# Filamint_Schematic_V4.net
KiCad netlist of a schematic drawn in EAGLE
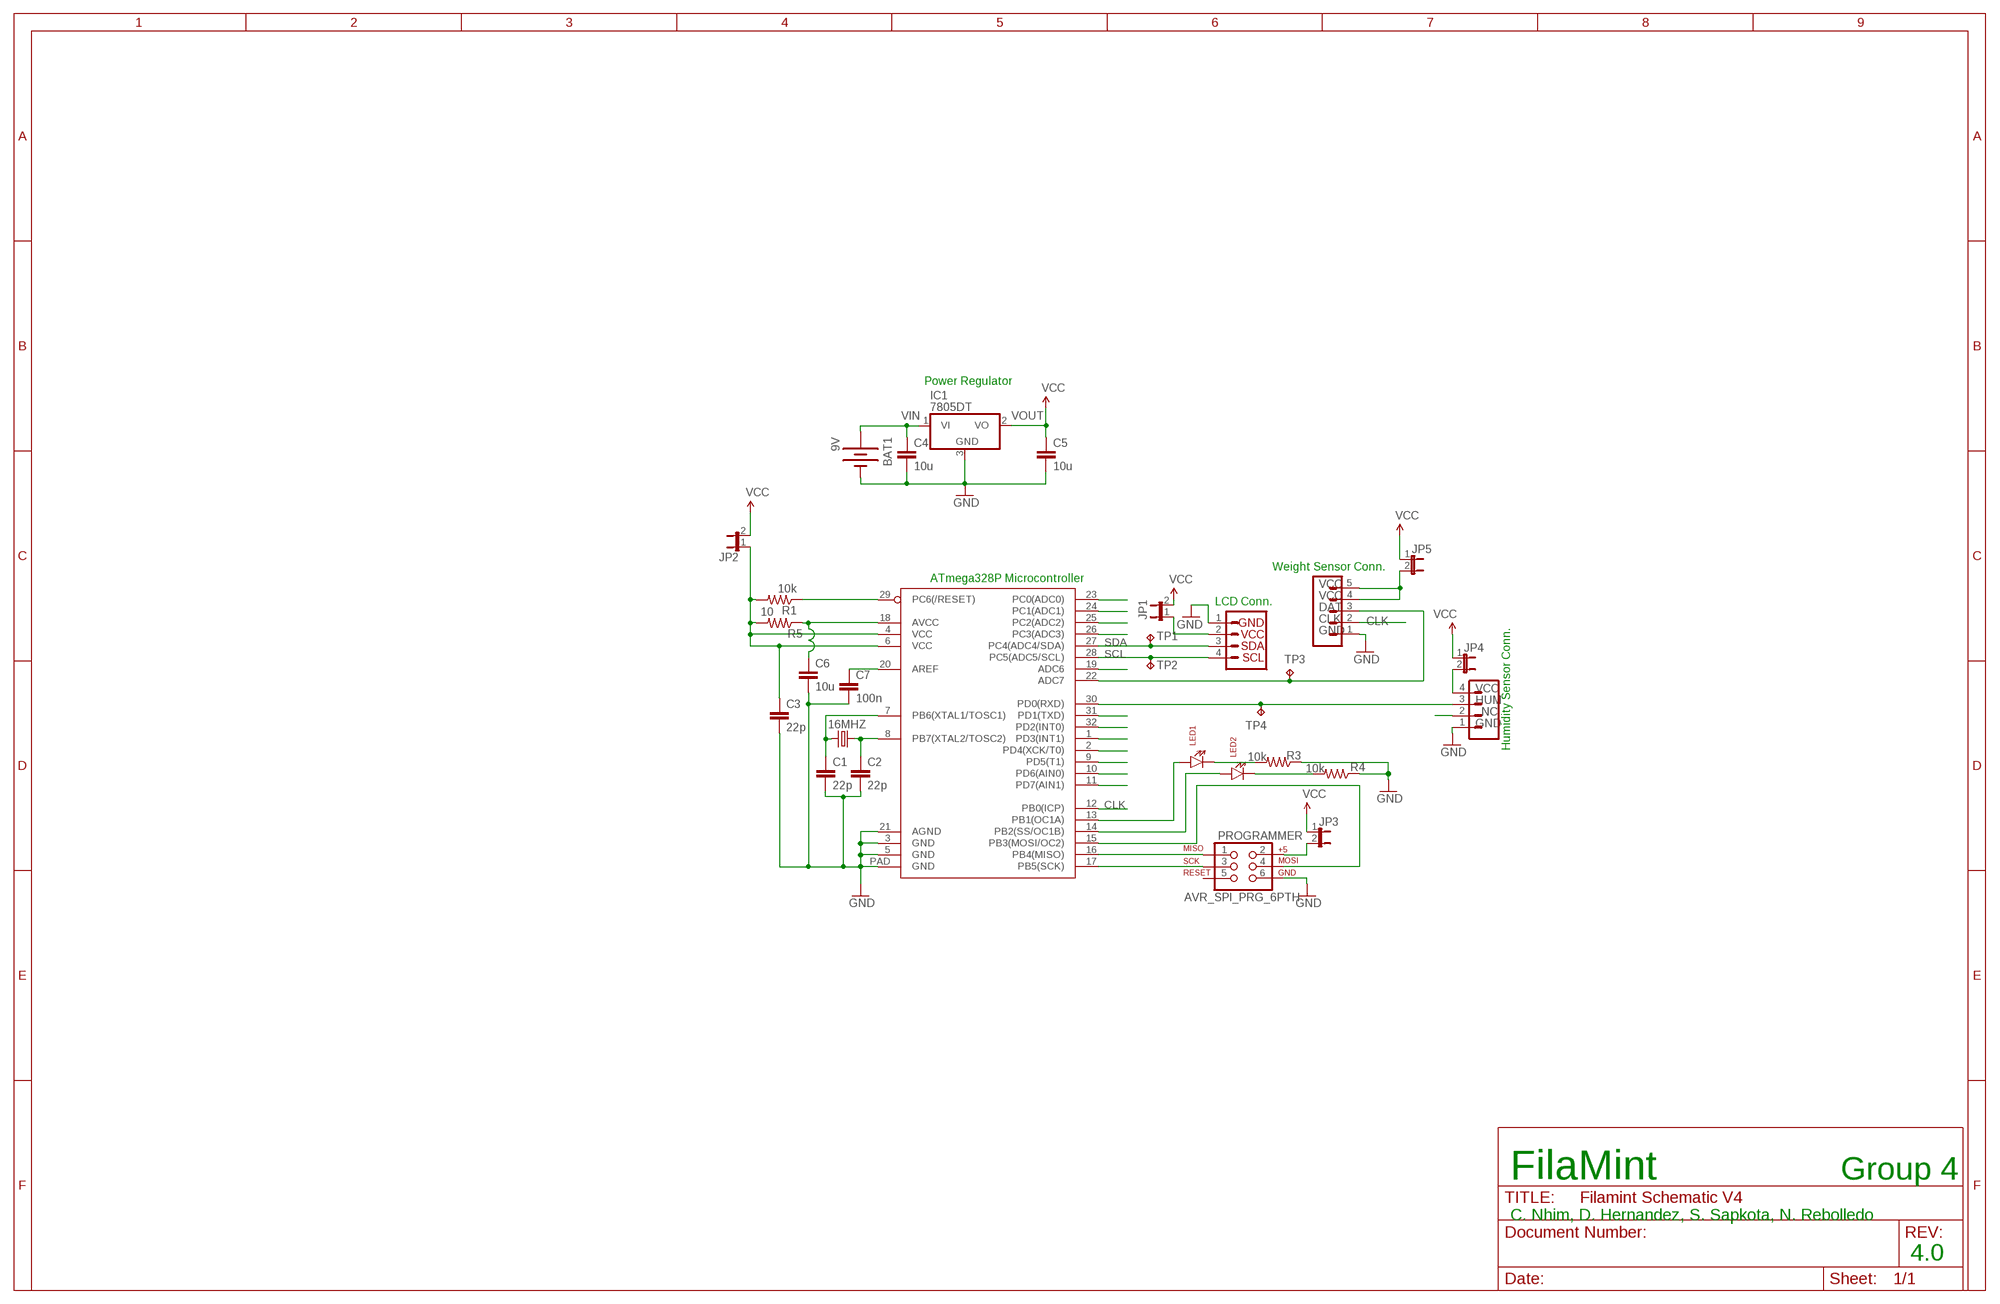
[diagram p0: schematic, sheet 1]

(export (version "E")
  (design (tool "Eeschema 10.0.6"))
  (components
    (comp (ref "16MHZ")
      (value "CSM-7X-DU")
      (footprint "eagle-import:CSM-7X-DU")
      (libsource (lib "eagle-import") (part "CSM-7X-DU"))
    )
    (comp (ref "BAT1")
      (value "9V")
      (footprint "eagle-import:BATTCON_9V")
      (libsource (lib "eagle-import") (part "BATTERY9V"))
    )
    (comp (ref "C1")
      (value "22p")
      (footprint "eagle-import:C025-024X044")
      (libsource (lib "eagle-import") (part "C-EU025-024X044"))
    )
    (comp (ref "C2")
      (value "22p")
      (footprint "eagle-import:C025-024X044")
      (libsource (lib "eagle-import") (part "C-EU025-024X044"))
    )
    (comp (ref "C3")
      (value "22p")
      (footprint "eagle-import:C025-024X044")
      (libsource (lib "eagle-import") (part "C-EU025-024X044"))
    )
    (comp (ref "C4")
      (value "10u")
      (footprint "eagle-import:C025-024X044")
      (libsource (lib "eagle-import") (part "C-EU025-024X044"))
    )
    (comp (ref "C5")
      (value "10u")
      (footprint "eagle-import:C025-024X044")
      (libsource (lib "eagle-import") (part "C-EU025-024X044"))
    )
    (comp (ref "C6")
      (value "10u")
      (footprint "eagle-import:C025-024X044")
      (libsource (lib "eagle-import") (part "C-EU025-024X044"))
    )
    (comp (ref "C7")
      (value "100n")
      (footprint "eagle-import:C025-024X044")
      (libsource (lib "eagle-import") (part "C-EU025-024X044"))
    )
    (comp (ref "DHT22")
      (value "M04SMD2")
      (footprint "eagle-import:1X04-1MM-RA")
      (libsource (lib "eagle-import") (part "M04SMD2"))
    )
    (comp (ref "HX711")
      (value "M05SMD")
      (footprint "eagle-import:1X05-1MM")
      (libsource (lib "eagle-import") (part "M05SMD"))
    )
    (comp (ref "IC1")
      (value "7805DT")
      (footprint "eagle-import:TO252")
      (libsource (lib "eagle-import") (part "78DT05"))
    )
    (comp (ref "JP1")
      (value "JP1E")
      (footprint "eagle-import:JP1")
      (libsource (lib "eagle-import") (part "JP1E"))
    )
    (comp (ref "JP2")
      (value "JP1E")
      (footprint "eagle-import:JP1")
      (libsource (lib "eagle-import") (part "JP1E"))
    )
    (comp (ref "JP3")
      (value "JP1E")
      (footprint "eagle-import:JP1")
      (libsource (lib "eagle-import") (part "JP1E"))
    )
    (comp (ref "JP4")
      (value "JP1E")
      (footprint "eagle-import:JP1")
      (libsource (lib "eagle-import") (part "JP1E"))
    )
    (comp (ref "JP5")
      (value "JP1E")
      (footprint "eagle-import:JP1")
      (libsource (lib "eagle-import") (part "JP1E"))
    )
    (comp (ref "LCD")
      (value "I2C_STANDARD")
      (footprint "eagle-import:1X04")
      (libsource (lib "eagle-import") (part "I2C_STANDARD"))
    )
    (comp (ref "LED1")
      (value "LTE-302")
      (footprint "eagle-import:LTE-302")
      (libsource (lib "eagle-import") (part "LTE-302"))
    )
    (comp (ref "LED2")
      (value "LTE-302")
      (footprint "eagle-import:LTE-302")
      (libsource (lib "eagle-import") (part "LTE-302"))
    )
    (comp (ref "MICROCONTROLLER")
      (value "ATMEGA328P_MLFMLF32")
      (footprint "eagle-import:MLF32-PAD")
      (libsource (lib "eagle-import") (part "ATMEGA328P_MLFMLF32"))
    )
    (comp (ref "PROGRAMMER")
      (value "AVR_SPI_PRG_6PTH")
      (footprint "eagle-import:2X3")
      (libsource (lib "eagle-import") (part "AVR_SPI_PRG_6PTH"))
    )
    (comp (ref "R1")
      (value "10k")
      (footprint "eagle-import:0204_5")
      (libsource (lib "eagle-import") (part "R-US_0204/5"))
    )
    (comp (ref "R3")
      (value "10k")
      (footprint "eagle-import:0204_5")
      (libsource (lib "eagle-import") (part "R-US_0204/5"))
    )
    (comp (ref "R4")
      (value "10k")
      (footprint "eagle-import:0204_5")
      (libsource (lib "eagle-import") (part "R-US_0204/5"))
    )
    (comp (ref "R5")
      (value "10")
      (footprint "eagle-import:0204_5")
      (libsource (lib "eagle-import") (part "R-US_0204/5"))
    )
    (comp (ref "TP1")
      (value "TPB1,27")
      (footprint "eagle-import:B1,27")
      (libsource (lib "eagle-import") (part "TPB1,27"))
    )
    (comp (ref "TP2")
      (value "TPB1,27")
      (footprint "eagle-import:B1,27")
      (libsource (lib "eagle-import") (part "TPB1,27"))
    )
    (comp (ref "TP3")
      (value "TPB1,27")
      (footprint "eagle-import:B1,27")
      (libsource (lib "eagle-import") (part "TPB1,27"))
    )
    (comp (ref "TP4")
      (value "TPB1,27")
      (footprint "eagle-import:B1,27")
      (libsource (lib "eagle-import") (part "TPB1,27"))
    )
  )
  (nets
    (net (code "1") (name "/CLK") (class "Default")
      (node (ref "HX711") (pin "2") (pinfunction "2_2") (pintype "passive"))
      (node (ref "MICROCONTROLLER") (pin "12") (pinfunction "PB0(ICP)_12") (pintype "bidirectional"))
    )
    (net (code "2") (name "/NC") (class "Default")
      (node (ref "DHT22") (pin "2") (pinfunction "2_2") (pintype "passive"))
    )
    (net (code "3") (name "/SCL") (class "Default")
      (node (ref "LCD") (pin "4") (pinfunction "4_4") (pintype "passive"))
      (node (ref "MICROCONTROLLER") (pin "28") (pinfunction "PC5(ADC5/SCL)_28") (pintype "bidirectional"))
      (node (ref "TP2") (pin "TP") (pinfunction "TP_TP") (pintype "input"))
    )
    (net (code "4") (name "/SDA") (class "Default")
      (node (ref "LCD") (pin "3") (pinfunction "3_3") (pintype "passive"))
      (node (ref "MICROCONTROLLER") (pin "27") (pinfunction "PC4(ADC4/SDA)_27") (pintype "bidirectional"))
      (node (ref "TP1") (pin "TP") (pinfunction "TP_TP") (pintype "input"))
    )
    (net (code "5") (name "/VIN") (class "Default")
      (node (ref "BAT1") (pin "+") (pinfunction "+_+") (pintype "power_in"))
      (node (ref "C4") (pin "1") (pinfunction "1_1") (pintype "passive"))
      (node (ref "IC1") (pin "1") (pinfunction "VI_1") (pintype "input"))
    )
    (net (code "6") (name "GND") (class "Default")
      (node (ref "BAT1") (pin "-") (pinfunction "-_-") (pintype "power_in"))
      (node (ref "C1") (pin "2") (pinfunction "2_2") (pintype "passive"))
      (node (ref "C2") (pin "2") (pinfunction "2_2") (pintype "passive"))
      (node (ref "C3") (pin "2") (pinfunction "2_2") (pintype "passive"))
      (node (ref "C4") (pin "2") (pinfunction "2_2") (pintype "passive"))
      (node (ref "C5") (pin "2") (pinfunction "2_2") (pintype "passive"))
      (node (ref "C6") (pin "2") (pinfunction "2_2") (pintype "passive"))
      (node (ref "C7") (pin "2") (pinfunction "2_2") (pintype "passive"))
      (node (ref "DHT22") (pin "1") (pinfunction "1_1") (pintype "passive"))
      (node (ref "HX711") (pin "1") (pinfunction "1_1") (pintype "passive"))
      (node (ref "IC1") (pin "3") (pinfunction "GND_3") (pintype "passive"))
      (node (ref "LCD") (pin "1") (pinfunction "1_1") (pintype "passive"))
      (node (ref "MICROCONTROLLER") (pin "21") (pinfunction "AGND_21") (pintype "bidirectional"))
      (node (ref "MICROCONTROLLER") (pin "3") (pinfunction "GND_3") (pintype "bidirectional"))
      (node (ref "MICROCONTROLLER") (pin "5") (pinfunction "GND_5") (pintype "bidirectional"))
      (node (ref "MICROCONTROLLER") (pin "PAD") (pinfunction "GND_PAD") (pintype "bidirectional"))
      (node (ref "PROGRAMMER") (pin "6") (pinfunction "6_6") (pintype "passive"))
      (node (ref "R3") (pin "1") (pinfunction "1_1") (pintype "passive"))
      (node (ref "R4") (pin "1") (pinfunction "1_1") (pintype "passive"))
    )
    (net (code "7") (name "Net-(C3-Pad1)") (class "Default")
      (node (ref "C3") (pin "1") (pinfunction "1_1") (pintype "passive"))
      (node (ref "JP2") (pin "1") (pinfunction "1_1") (pintype "passive"))
      (node (ref "MICROCONTROLLER") (pin "4") (pinfunction "VCC_4") (pintype "bidirectional"))
      (node (ref "MICROCONTROLLER") (pin "6") (pinfunction "VCC_6") (pintype "bidirectional"))
      (node (ref "R1") (pin "2") (pinfunction "2_2") (pintype "passive"))
      (node (ref "R5") (pin "2") (pinfunction "2_2") (pintype "passive"))
    )
    (net (code "8") (name "Net-(DHT22-Pad4)") (class "Default")
      (node (ref "DHT22") (pin "4") (pinfunction "4_4") (pintype "passive"))
      (node (ref "JP4") (pin "2") (pinfunction "2_2") (pintype "passive"))
    )
    (net (code "9") (name "Net-(HX711-Pad4)") (class "Default")
      (node (ref "HX711") (pin "4") (pinfunction "4_4") (pintype "passive"))
      (node (ref "HX711") (pin "5") (pinfunction "5_5") (pintype "passive"))
      (node (ref "JP5") (pin "2") (pinfunction "2_2") (pintype "passive"))
    )
    (net (code "10") (name "Net-(JP1-Pad1)") (class "Default")
      (node (ref "JP1") (pin "1") (pinfunction "1_1") (pintype "passive"))
      (node (ref "LCD") (pin "2") (pinfunction "2_2") (pintype "passive"))
    )
    (net (code "11") (name "Net-(JP3-Pad2)") (class "Default")
      (node (ref "JP3") (pin "2") (pinfunction "2_2") (pintype "passive"))
      (node (ref "PROGRAMMER") (pin "2") (pinfunction "2_2") (pintype "passive"))
    )
    (net (code "12") (name "Net-(LED1-PadC)") (class "Default")
      (node (ref "LED1") (pin "C") (pinfunction "C_C") (pintype "bidirectional"))
      (node (ref "R3") (pin "2") (pinfunction "2_2") (pintype "passive"))
    )
    (net (code "13") (name "Net-(LED2-PadC)") (class "Default")
      (node (ref "LED2") (pin "C") (pinfunction "C_C") (pintype "bidirectional"))
      (node (ref "R4") (pin "2") (pinfunction "2_2") (pintype "passive"))
    )
    (net (code "14") (name "Net-(MICROCONTROLLER-ADC7)") (class "Default")
      (node (ref "HX711") (pin "3") (pinfunction "3_3") (pintype "passive"))
      (node (ref "MICROCONTROLLER") (pin "22") (pinfunction "ADC7_22") (pintype "bidirectional"))
      (node (ref "TP3") (pin "TP") (pinfunction "TP_TP") (pintype "input"))
    )
    (net (code "15") (name "Net-(MICROCONTROLLER-AREF)") (class "Default")
      (node (ref "C7") (pin "1") (pinfunction "1_1") (pintype "passive"))
      (node (ref "MICROCONTROLLER") (pin "20") (pinfunction "AREF_20") (pintype "bidirectional"))
    )
    (net (code "16") (name "Net-(MICROCONTROLLER-AVCC)") (class "Default")
      (node (ref "C6") (pin "1") (pinfunction "1_1") (pintype "passive"))
      (node (ref "MICROCONTROLLER") (pin "18") (pinfunction "AVCC_18") (pintype "bidirectional"))
      (node (ref "R5") (pin "1") (pinfunction "1_1") (pintype "passive"))
    )
    (net (code "17") (name "Net-(MICROCONTROLLER-PB1(OC1A))") (class "Default")
      (node (ref "LED1") (pin "A") (pinfunction "A_A") (pintype "bidirectional"))
      (node (ref "MICROCONTROLLER") (pin "13") (pinfunction "PB1(OC1A)_13") (pintype "bidirectional"))
    )
    (net (code "18") (name "Net-(MICROCONTROLLER-PB2(SS{slash}OC1B))") (class "Default")
      (node (ref "LED2") (pin "A") (pinfunction "A_A") (pintype "bidirectional"))
      (node (ref "MICROCONTROLLER") (pin "14") (pinfunction "PB2(SS/OC1B)_14") (pintype "bidirectional"))
    )
    (net (code "19") (name "Net-(MICROCONTROLLER-PB3(MOSI{slash}OC2))") (class "Default")
      (node (ref "MICROCONTROLLER") (pin "15") (pinfunction "PB3(MOSI/OC2)_15") (pintype "bidirectional"))
      (node (ref "PROGRAMMER") (pin "4") (pinfunction "4_4") (pintype "passive"))
    )
    (net (code "20") (name "Net-(MICROCONTROLLER-PB4(MISO))") (class "Default")
      (node (ref "MICROCONTROLLER") (pin "16") (pinfunction "PB4(MISO)_16") (pintype "bidirectional"))
      (node (ref "PROGRAMMER") (pin "1") (pinfunction "1_1") (pintype "passive"))
    )
    (net (code "21") (name "Net-(MICROCONTROLLER-PB5(SCK))") (class "Default")
      (node (ref "MICROCONTROLLER") (pin "17") (pinfunction "PB5(SCK)_17") (pintype "bidirectional"))
      (node (ref "PROGRAMMER") (pin "3") (pinfunction "3_3") (pintype "passive"))
    )
    (net (code "22") (name "Net-(MICROCONTROLLER-PB6(XTAL1{slash}TOSC1))") (class "Default")
      (node (ref "16MHZ") (pin "2") (pinfunction "2_2") (pintype "passive"))
      (node (ref "C1") (pin "1") (pinfunction "1_1") (pintype "passive"))
      (node (ref "MICROCONTROLLER") (pin "7") (pinfunction "PB6(XTAL1/TOSC1)_7") (pintype "bidirectional"))
    )
    (net (code "23") (name "Net-(MICROCONTROLLER-PB7(XTAL2{slash}TOSC2))") (class "Default")
      (node (ref "16MHZ") (pin "1") (pinfunction "1_1") (pintype "passive"))
      (node (ref "C2") (pin "1") (pinfunction "1_1") (pintype "passive"))
      (node (ref "MICROCONTROLLER") (pin "8") (pinfunction "PB7(XTAL2/TOSC2)_8") (pintype "bidirectional"))
    )
    (net (code "24") (name "Net-(MICROCONTROLLER-PC6({slash}RESET))") (class "Default")
      (node (ref "MICROCONTROLLER") (pin "29") (pinfunction "PC6(/RESET)_29") (pintype "bidirectional"))
      (node (ref "R1") (pin "1") (pinfunction "1_1") (pintype "passive"))
    )
    (net (code "25") (name "Net-(MICROCONTROLLER-PD0(RXD))") (class "Default")
      (node (ref "DHT22") (pin "3") (pinfunction "3_3") (pintype "passive"))
      (node (ref "MICROCONTROLLER") (pin "30") (pinfunction "PD0(RXD)_30") (pintype "bidirectional"))
      (node (ref "TP4") (pin "TP") (pinfunction "TP_TP") (pintype "input"))
    )
    (net (code "26") (name "VCC") (class "Default")
      (node (ref "C5") (pin "1") (pinfunction "1_1") (pintype "passive"))
      (node (ref "IC1") (pin "2") (pinfunction "VO_2") (pintype "passive"))
      (node (ref "JP1") (pin "2") (pinfunction "2_2") (pintype "passive"))
      (node (ref "JP2") (pin "2") (pinfunction "2_2") (pintype "passive"))
      (node (ref "JP3") (pin "1") (pinfunction "1_1") (pintype "passive"))
      (node (ref "JP4") (pin "1") (pinfunction "1_1") (pintype "passive"))
      (node (ref "JP5") (pin "1") (pinfunction "1_1") (pintype "passive"))
    )
    (net (code "27") (name "unconnected-(MICROCONTROLLER-ADC6-Pad19)") (class "Default")
      (node (ref "MICROCONTROLLER") (pin "19") (pinfunction "ADC6_19") (pintype "bidirectional"))
    )
    (net (code "28") (name "unconnected-(MICROCONTROLLER-PC0(ADC0)-Pad23)") (class "Default")
      (node (ref "MICROCONTROLLER") (pin "23") (pinfunction "PC0(ADC0)_23") (pintype "bidirectional"))
    )
    (net (code "29") (name "unconnected-(MICROCONTROLLER-PC1(ADC1)-Pad24)") (class "Default")
      (node (ref "MICROCONTROLLER") (pin "24") (pinfunction "PC1(ADC1)_24") (pintype "bidirectional"))
    )
    (net (code "30") (name "unconnected-(MICROCONTROLLER-PC2(ADC2)-Pad25)") (class "Default")
      (node (ref "MICROCONTROLLER") (pin "25") (pinfunction "PC2(ADC2)_25") (pintype "bidirectional"))
    )
    (net (code "31") (name "unconnected-(MICROCONTROLLER-PC3(ADC3)-Pad26)") (class "Default")
      (node (ref "MICROCONTROLLER") (pin "26") (pinfunction "PC3(ADC3)_26") (pintype "bidirectional"))
    )
    (net (code "32") (name "unconnected-(MICROCONTROLLER-PD1(TXD)-Pad31)") (class "Default")
      (node (ref "MICROCONTROLLER") (pin "31") (pinfunction "PD1(TXD)_31") (pintype "bidirectional"))
    )
    (net (code "33") (name "unconnected-(MICROCONTROLLER-PD2(INT0)-Pad32)") (class "Default")
      (node (ref "MICROCONTROLLER") (pin "32") (pinfunction "PD2(INT0)_32") (pintype "bidirectional"))
    )
    (net (code "34") (name "unconnected-(MICROCONTROLLER-PD3(INT1)-Pad1)") (class "Default")
      (node (ref "MICROCONTROLLER") (pin "1") (pinfunction "PD3(INT1)_1") (pintype "bidirectional"))
    )
    (net (code "35") (name "unconnected-(MICROCONTROLLER-PD4(XCK{slash}T0)-Pad2)") (class "Default")
      (node (ref "MICROCONTROLLER") (pin "2") (pinfunction "PD4(XCK/T0)_2") (pintype "bidirectional"))
    )
    (net (code "36") (name "unconnected-(MICROCONTROLLER-PD5(T1)-Pad9)") (class "Default")
      (node (ref "MICROCONTROLLER") (pin "9") (pinfunction "PD5(T1)_9") (pintype "bidirectional"))
    )
    (net (code "37") (name "unconnected-(MICROCONTROLLER-PD6(AIN0)-Pad10)") (class "Default")
      (node (ref "MICROCONTROLLER") (pin "10") (pinfunction "PD6(AIN0)_10") (pintype "bidirectional"))
    )
    (net (code "38") (name "unconnected-(MICROCONTROLLER-PD7(AIN1)-Pad11)") (class "Default")
      (node (ref "MICROCONTROLLER") (pin "11") (pinfunction "PD7(AIN1)_11") (pintype "bidirectional"))
    )
    (net (code "39") (name "unconnected-(PROGRAMMER-Pad5)") (class "Default")
      (node (ref "PROGRAMMER") (pin "5") (pinfunction "5_5") (pintype "passive"))
    )
  )
)
